# WidgetEsp8266RGBv4Strip.net
KiCad netlist of a schematic drawn in EAGLE
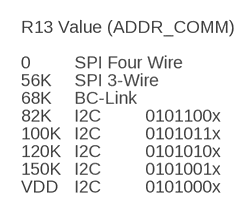
[diagram p0: schematic, sheet 1, part 1 of 3]
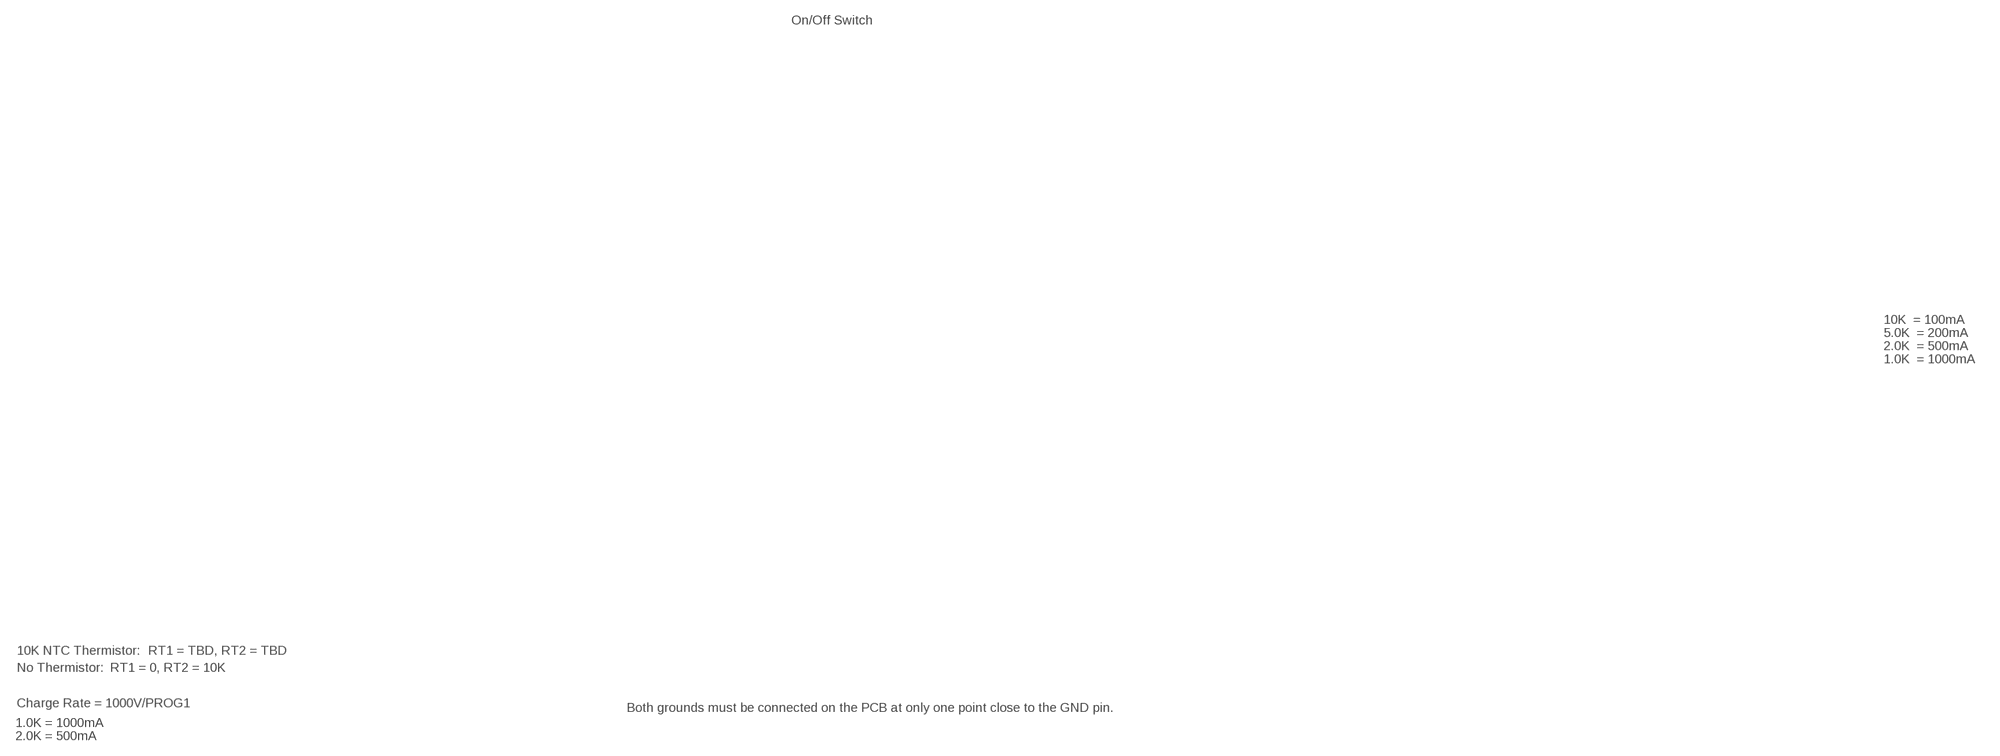
[diagram p1: schematic, sheet 1, part 2 of 3]
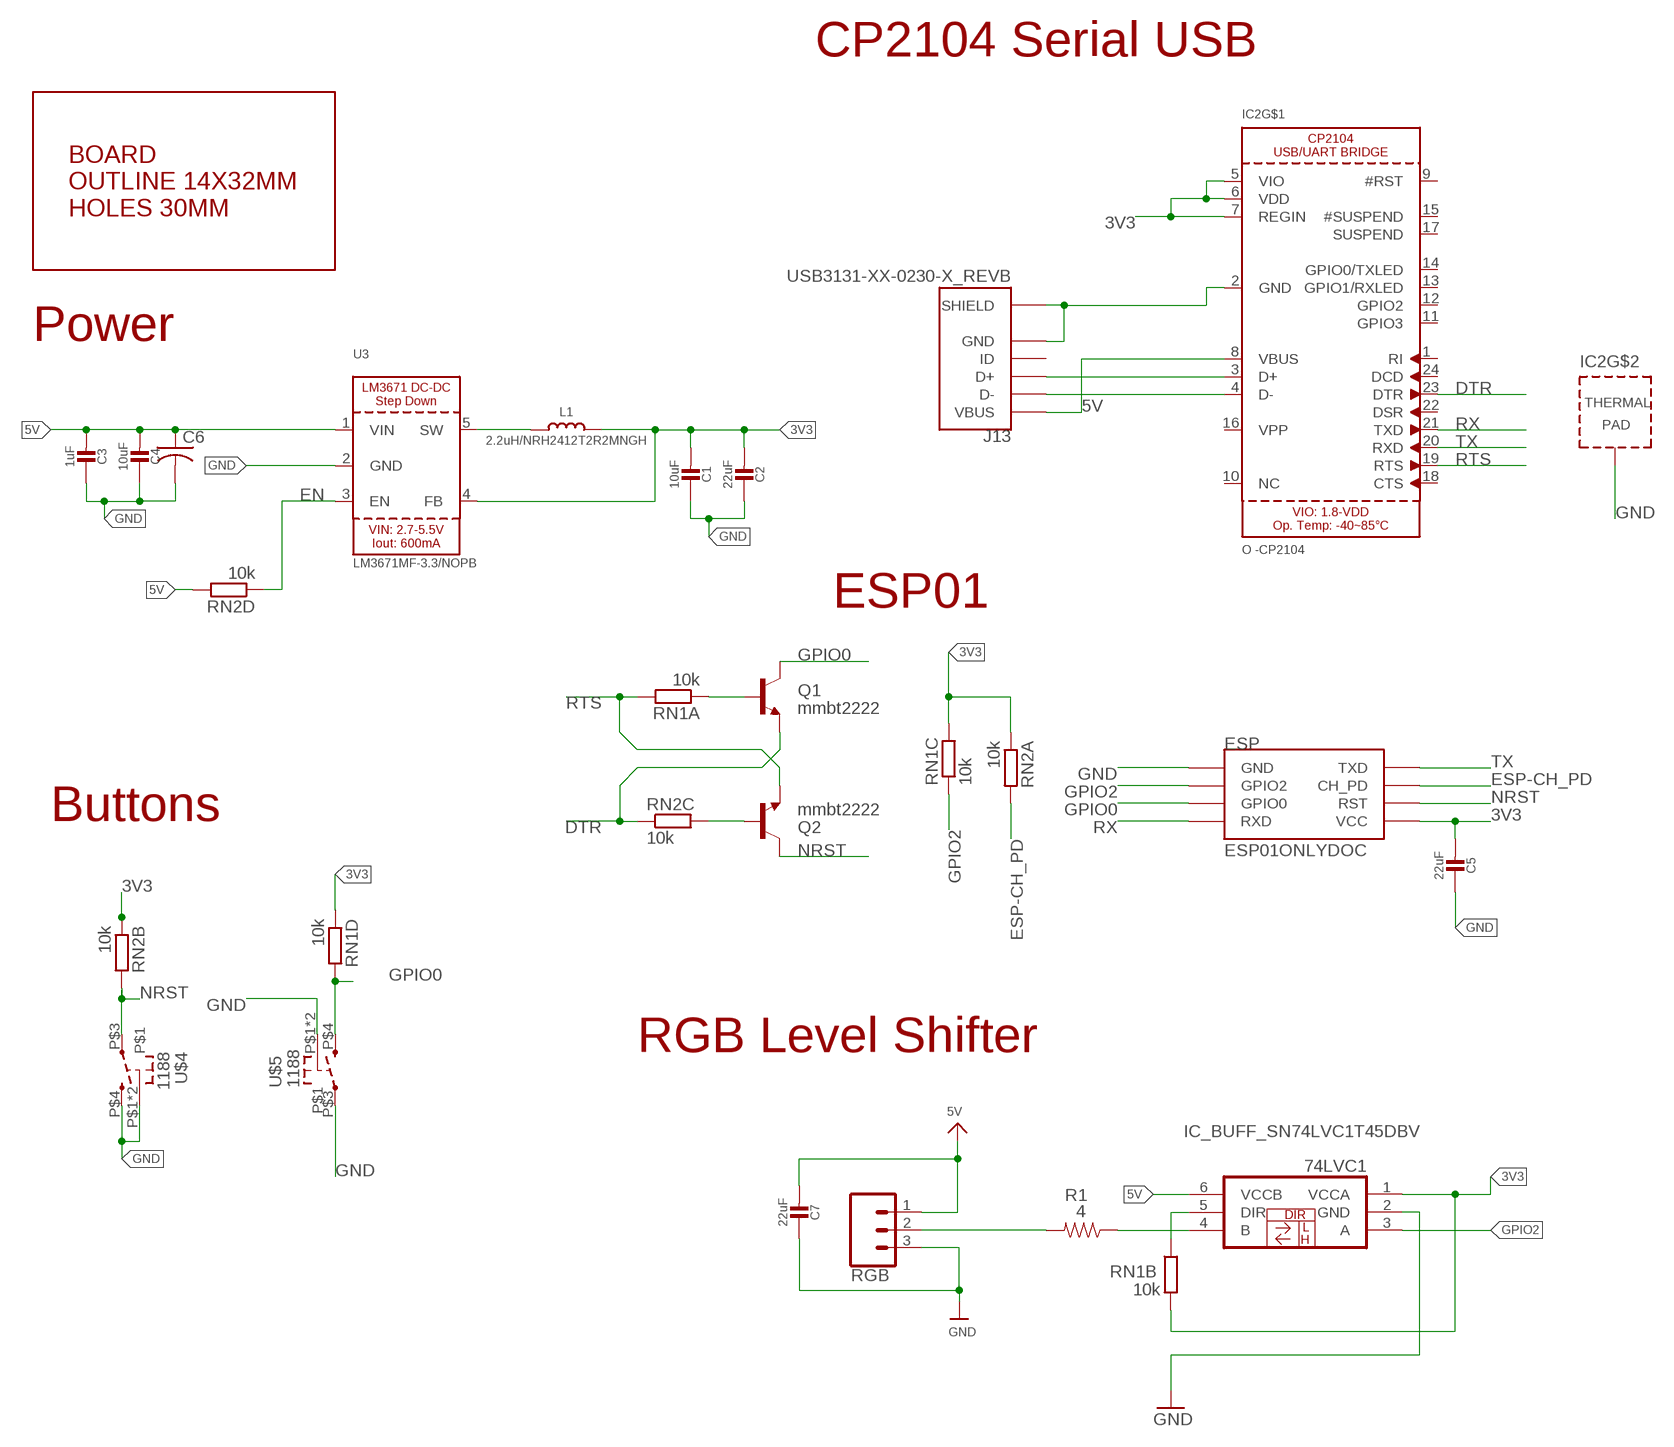
[diagram p2: schematic, sheet 1, part 3 of 3]

(export (version "E")
  (design (tool "Eeschema 10.0.6"))
  (components
    (comp (ref "74LVC1")
      (value "IC_BUFF_SN74LVC1T45DBV")
      (footprint "eagle-import:DBV-R-PDSO-G6")
      (libsource (lib "eagle-import") (part "IC_BUFF_SN74LVC1T45DBV"))
    )
    (comp (ref "C1")
      (value "10uF")
      (footprint "eagle-import:0805-NO")
      (libsource (lib "eagle-import") (part "CAP_CERAMIC0805-NOOUTLINE"))
    )
    (comp (ref "C2")
      (value "22uF")
      (footprint "eagle-import:0805-NO")
      (libsource (lib "eagle-import") (part "CAP_CERAMIC0805-NOOUTLINE"))
    )
    (comp (ref "C3")
      (value "1uF")
      (footprint "eagle-import:0805-NO")
      (libsource (lib "eagle-import") (part "CAP_CERAMIC0805-NOOUTLINE"))
    )
    (comp (ref "C4")
      (value "10uF")
      (footprint "eagle-import:0805-NO")
      (libsource (lib "eagle-import") (part "CAP_CERAMIC0805-NOOUTLINE"))
    )
    (comp (ref "C5")
      (value "22uF")
      (footprint "eagle-import:0805-NO")
      (libsource (lib "eagle-import") (part "CAP_CERAMIC0805-NOOUTLINE"))
    )
    (comp (ref "C6")
      (value "C-USC3225")
      (footprint "eagle-import:C3225")
      (libsource (lib "eagle-import") (part "C-USC3225"))
    )
    (comp (ref "C7")
      (value "22uF")
      (footprint "eagle-import:0805-NO")
      (libsource (lib "eagle-import") (part "CAP_CERAMIC0805-NOOUTLINE"))
    )
    (comp (ref "ESP")
      (value "ESP01ONLYDOC")
      (footprint "eagle-import:ESP01-NONOSILK")
      (libsource (lib "eagle-import") (part "ESP01ONLYDOC"))
    )
    (comp (ref "IC2")
      (value "O -CP2104")
      (footprint "eagle-import:QFN24_4MM_SMSC")
      (libsource (lib "eagle-import") (part "CP2104"))
    )
    (comp (ref "J13")
      (value "USB3131-XX-0230-X_REVB")
      (footprint "eagle-import:GCT_USB3131-XX-0230-X_REVB")
      (fields
        (field (name "MF") "Global Connector Technology")
        (field (name "MP") "USB3131-30-0230-A")
        (field (name "SPICEPREFIX") "X")
      )
      (libsource (lib "eagle-import") (part "USB3131-XX-0230-X_REVB"))
    )
    (comp (ref "L1")
      (value "2.2uH/NRH2412T2R2MNGH")
      (footprint "eagle-import:INDUCTOR_TAIYOYUDEN_NRH2412T")
      (libsource (lib "eagle-import") (part "INDUCTORNRH2412T"))
    )
    (comp (ref "Q1")
      (value "mmbt2222")
      (footprint "eagle-import:SOT23-3")
      (libsource (lib "eagle-import") (part "TRANSISTOR_NPNSOT23-3"))
    )
    (comp (ref "Q2")
      (value "mmbt2222")
      (footprint "eagle-import:SOT23-3")
      (libsource (lib "eagle-import") (part "TRANSISTOR_NPNSOT23-3"))
    )
    (comp (ref "R1")
      (value "4")
      (footprint "eagle-import:0805")
      (libsource (lib "eagle-import") (part "RESISTOR0805-RES"))
    )
    (comp (ref "RGB")
      (value "CONN_03LONGPADS")
      (footprint "eagle-import:1X03_LONGPADS")
      (libsource (lib "eagle-import") (part "CONN_03LONGPADS"))
    )
    (comp (ref "RN1")
      (value "10k")
      (footprint "eagle-import:RN8P-4R-CRA06S")
      (libsource (lib "eagle-import") (part "RESISTOR_ARRAY_4"))
    )
    (comp (ref "RN2")
      (value "10k")
      (footprint "eagle-import:RN8P-4R-CRA06S")
      (libsource (lib "eagle-import") (part "RESISTOR_ARRAY_4"))
    )
    (comp (ref "U$4")
      (value "1188")
      (footprint "eagle-import:1188")
      (libsource (lib "eagle-import") (part "1188"))
    )
    (comp (ref "U$5")
      (value "1188")
      (footprint "eagle-import:1188")
      (libsource (lib "eagle-import") (part "1188"))
    )
    (comp (ref "U$7")
      (value "BOARD14X32")
      (footprint "eagle-import:14X32")
      (libsource (lib "eagle-import") (part "BOARD14X32"))
    )
    (comp (ref "U3")
      (value "LM3671MF-3.3/NOPB")
      (footprint "eagle-import:SOT23-5")
      (libsource (lib "eagle-import") (part "VREG_LM3671"))
    )
  )
  (nets
    (net (code "1") (name "/DTR") (class "Default")
      (node (ref "IC2") (pin "23") (pinfunction "DTR_23") (pintype "output"))
      (node (ref "Q1") (pin "2") (pinfunction "E_2") (pintype "passive"))
      (node (ref "RN2") (pin "3") (pinfunction "1_3") (pintype "passive"))
    )
    (net (code "2") (name "/EN") (class "Default")
      (node (ref "RN2") (pin "4") (pinfunction "1_4") (pintype "passive"))
      (node (ref "U3") (pin "3") (pinfunction "EN_3") (pintype "input"))
    )
    (net (code "3") (name "/ESP-CH_PD") (class "Default")
      (node (ref "ESP") (pin "CH_PD") (pinfunction "CH_PD_CH_PD") (pintype "bidirectional"))
      (node (ref "RN2") (pin "8") (pinfunction "2_8") (pintype "passive"))
    )
    (net (code "4") (name "/GPIO0") (class "Default")
      (node (ref "ESP") (pin "GPIO0") (pinfunction "GPIO0_GPIO0") (pintype "bidirectional"))
      (node (ref "Q1") (pin "3") (pinfunction "C_3") (pintype "passive"))
      (node (ref "RN1") (pin "5") (pinfunction "2_5") (pintype "passive"))
      (node (ref "U$5") (pin "P$4") (pinfunction "3_P$4") (pintype "passive"))
    )
    (net (code "5") (name "/NRST") (class "Default")
      (node (ref "ESP") (pin "RST") (pinfunction "RST_RST") (pintype "bidirectional"))
      (node (ref "Q2") (pin "3") (pinfunction "C_3") (pintype "passive"))
      (node (ref "RN2") (pin "7") (pinfunction "2_7") (pintype "passive"))
      (node (ref "U$4") (pin "P$3") (pinfunction "1_P$3") (pintype "passive"))
    )
    (net (code "6") (name "/RTS") (class "Default")
      (node (ref "IC2") (pin "19") (pinfunction "RTS_19") (pintype "output"))
      (node (ref "Q2") (pin "2") (pinfunction "E_2") (pintype "passive"))
      (node (ref "RN1") (pin "8") (pinfunction "2_8") (pintype "passive"))
    )
    (net (code "7") (name "/RX") (class "Default")
      (node (ref "ESP") (pin "RX") (pinfunction "RXD_RX") (pintype "bidirectional"))
      (node (ref "IC2") (pin "21") (pinfunction "TXD_21") (pintype "output"))
    )
    (net (code "8") (name "/TX") (class "Default")
      (node (ref "ESP") (pin "TX") (pinfunction "TXD_TX") (pintype "bidirectional"))
      (node (ref "IC2") (pin "20") (pinfunction "RXD_20") (pintype "input"))
    )
    (net (code "9") (name "3V3") (class "Default")
      (node (ref "74LVC1") (pin "1") (pinfunction "VCCA_1") (pintype "power_in"))
      (node (ref "C1") (pin "2") (pinfunction "2_2") (pintype "passive"))
      (node (ref "C2") (pin "2") (pinfunction "2_2") (pintype "passive"))
      (node (ref "C5") (pin "2") (pinfunction "2_2") (pintype "passive"))
      (node (ref "ESP") (pin "VCC") (pinfunction "VCC_VCC") (pintype "bidirectional"))
      (node (ref "IC2") (pin "5") (pinfunction "VIO_5") (pintype "power_in"))
      (node (ref "IC2") (pin "6") (pinfunction "VDD_6") (pintype "power_in"))
      (node (ref "IC2") (pin "7") (pinfunction "REGIN_7") (pintype "power_in"))
      (node (ref "L1") (pin "2") (pinfunction "2_2") (pintype "passive"))
      (node (ref "RN1") (pin "4") (pinfunction "1_4") (pintype "passive"))
      (node (ref "RN1") (pin "6") (pinfunction "2_6") (pintype "passive"))
      (node (ref "RN1") (pin "7") (pinfunction "2_7") (pintype "passive"))
      (node (ref "RN2") (pin "1") (pinfunction "1_1") (pintype "passive"))
      (node (ref "RN2") (pin "2") (pinfunction "1_2") (pintype "passive"))
      (node (ref "U3") (pin "4") (pinfunction "FB_4") (pintype "power_in"))
    )
    (net (code "10") (name "5V") (class "Default")
      (node (ref "74LVC1") (pin "6") (pinfunction "VCCB_6") (pintype "power_in"))
      (node (ref "C3") (pin "2") (pinfunction "2_2") (pintype "passive"))
      (node (ref "C4") (pin "2") (pinfunction "2_2") (pintype "passive"))
      (node (ref "C6") (pin "1") (pinfunction "1_1") (pintype "passive"))
      (node (ref "C7") (pin "2") (pinfunction "2_2") (pintype "passive"))
      (node (ref "IC2") (pin "8") (pinfunction "VBUS_8") (pintype "power_in"))
      (node (ref "J13") (pin "1") (pinfunction "VBUS_1") (pintype "power_in"))
      (node (ref "RGB") (pin "1") (pinfunction "1_1") (pintype "passive"))
      (node (ref "RN2") (pin "5") (pinfunction "2_5") (pintype "passive"))
      (node (ref "U3") (pin "1") (pinfunction "VIN_1") (pintype "power_in"))
    )
    (net (code "11") (name "GND") (class "Default")
      (node (ref "74LVC1") (pin "2") (pinfunction "GND_2") (pintype "power_in"))
      (node (ref "C1") (pin "1") (pinfunction "1_1") (pintype "passive"))
      (node (ref "C2") (pin "1") (pinfunction "1_1") (pintype "passive"))
      (node (ref "C3") (pin "1") (pinfunction "1_1") (pintype "passive"))
      (node (ref "C4") (pin "1") (pinfunction "1_1") (pintype "passive"))
      (node (ref "C5") (pin "1") (pinfunction "1_1") (pintype "passive"))
      (node (ref "C6") (pin "2") (pinfunction "2_2") (pintype "passive"))
      (node (ref "C7") (pin "1") (pinfunction "1_1") (pintype "passive"))
      (node (ref "ESP") (pin "GND") (pinfunction "GND_GND") (pintype "bidirectional"))
      (node (ref "IC2") (pin "2") (pinfunction "GND_2") (pintype "power_in"))
      (node (ref "IC2") (pin "THERM") (pinfunction "TP_THERM") (pintype "power_in"))
      (node (ref "J13") (pin "5") (pinfunction "GND_5") (pintype "power_in"))
      (node (ref "J13") (pin "6") (pinfunction "SHIELD_6") (pintype "passive"))
      (node (ref "J13") (pin "7") (pinfunction "SHIELD_7") (pintype "passive"))
      (node (ref "RGB") (pin "3") (pinfunction "3_3") (pintype "passive"))
      (node (ref "U$4") (pin "P$1") (pinfunction "P$1_P$1") (pintype "bidirectional"))
      (node (ref "U$4") (pin "P$2") (pinfunction "P$1_P$2") (pintype "bidirectional"))
      (node (ref "U$4") (pin "P$4") (pinfunction "3_P$4") (pintype "passive"))
      (node (ref "U$5") (pin "P$1") (pinfunction "P$1_P$1") (pintype "bidirectional"))
      (node (ref "U$5") (pin "P$2") (pinfunction "P$1_P$2") (pintype "bidirectional"))
      (node (ref "U$5") (pin "P$3") (pinfunction "1_P$3") (pintype "passive"))
      (node (ref "U3") (pin "2") (pinfunction "GND_2") (pintype "power_in"))
    )
    (net (code "12") (name "GPIO2") (class "Default")
      (node (ref "74LVC1") (pin "3") (pinfunction "A_3") (pintype "bidirectional"))
      (node (ref "ESP") (pin "GPIO2") (pinfunction "GPIO2_GPIO2") (pintype "bidirectional"))
      (node (ref "RN1") (pin "3") (pinfunction "1_3") (pintype "passive"))
    )
    (net (code "13") (name "Net-(74LVC1-B)") (class "Default")
      (node (ref "74LVC1") (pin "4") (pinfunction "B_4") (pintype "bidirectional"))
      (node (ref "R1") (pin "1") (pinfunction "1_1") (pintype "passive"))
    )
    (net (code "14") (name "Net-(74LVC1-DIR)") (class "Default")
      (node (ref "74LVC1") (pin "5") (pinfunction "DIR_5") (pintype "input"))
      (node (ref "RN1") (pin "2") (pinfunction "1_2") (pintype "passive"))
    )
    (net (code "15") (name "Net-(IC2A-D+)") (class "Default")
      (node (ref "IC2") (pin "3") (pinfunction "D+_3") (pintype "bidirectional"))
      (node (ref "J13") (pin "3") (pinfunction "D+_3") (pintype "bidirectional"))
    )
    (net (code "16") (name "Net-(IC2A-D-)") (class "Default")
      (node (ref "IC2") (pin "4") (pinfunction "D-_4") (pintype "bidirectional"))
      (node (ref "J13") (pin "2") (pinfunction "D-_2") (pintype "bidirectional"))
    )
    (net (code "17") (name "Net-(Q1-B)") (class "Default")
      (node (ref "Q1") (pin "1") (pinfunction "B_1") (pintype "passive"))
      (node (ref "RN1") (pin "1") (pinfunction "1_1") (pintype "passive"))
    )
    (net (code "18") (name "Net-(Q2-B)") (class "Default")
      (node (ref "Q2") (pin "1") (pinfunction "B_1") (pintype "passive"))
      (node (ref "RN2") (pin "6") (pinfunction "2_6") (pintype "passive"))
    )
    (net (code "19") (name "Net-(R1-Pad2)") (class "Default")
      (node (ref "R1") (pin "2") (pinfunction "2_2") (pintype "passive"))
      (node (ref "RGB") (pin "2") (pinfunction "2_2") (pintype "passive"))
    )
    (net (code "20") (name "Net-(U3-SW)") (class "Default")
      (node (ref "L1") (pin "1") (pinfunction "1_1") (pintype "passive"))
      (node (ref "U3") (pin "5") (pinfunction "SW_5") (pintype "output"))
    )
    (net (code "21") (name "unconnected-(IC2A-#RST-Pad9)") (class "Default")
      (node (ref "IC2") (pin "9") (pinfunction "#RST_9") (pintype "bidirectional"))
    )
    (net (code "22") (name "unconnected-(IC2A-#SUSPEND-Pad15)") (class "Default")
      (node (ref "IC2") (pin "15") (pinfunction "#SUSPEND_15") (pintype "output"))
    )
    (net (code "23") (name "unconnected-(IC2A-CTS-Pad18)") (class "Default")
      (node (ref "IC2") (pin "18") (pinfunction "CTS_18") (pintype "input"))
    )
    (net (code "24") (name "unconnected-(IC2A-DCD-Pad24)") (class "Default")
      (node (ref "IC2") (pin "24") (pinfunction "DCD_24") (pintype "input"))
    )
    (net (code "25") (name "unconnected-(IC2A-DSR-Pad22)") (class "Default")
      (node (ref "IC2") (pin "22") (pinfunction "DSR_22") (pintype "input"))
    )
    (net (code "26") (name "unconnected-(IC2A-GPIO0{slash}TXLED-Pad14)") (class "Default")
      (node (ref "IC2") (pin "14") (pinfunction "GPIO0/TXLED_14") (pintype "bidirectional"))
    )
    (net (code "27") (name "unconnected-(IC2A-GPIO1{slash}RXLED-Pad13)") (class "Default")
      (node (ref "IC2") (pin "13") (pinfunction "GPIO1/RXLED_13") (pintype "bidirectional"))
    )
    (net (code "28") (name "unconnected-(IC2A-GPIO2-Pad12)") (class "Default")
      (node (ref "IC2") (pin "12") (pinfunction "GPIO2_12") (pintype "bidirectional"))
    )
    (net (code "29") (name "unconnected-(IC2A-GPIO3-Pad11)") (class "Default")
      (node (ref "IC2") (pin "11") (pinfunction "GPIO3_11") (pintype "bidirectional"))
    )
    (net (code "30") (name "unconnected-(IC2A-NC-Pad10)") (class "Default")
      (node (ref "IC2") (pin "10") (pinfunction "NC_10") (pintype "no_connect"))
    )
    (net (code "31") (name "unconnected-(IC2A-RI-Pad1)") (class "Default")
      (node (ref "IC2") (pin "1") (pinfunction "RI_1") (pintype "input"))
    )
    (net (code "32") (name "unconnected-(IC2A-SUSPEND-Pad17)") (class "Default")
      (node (ref "IC2") (pin "17") (pinfunction "SUSPEND_17") (pintype "output"))
    )
    (net (code "33") (name "unconnected-(IC2A-VPP-Pad16)") (class "Default")
      (node (ref "IC2") (pin "16") (pinfunction "VPP_16") (pintype "bidirectional"))
    )
    (net (code "34") (name "unconnected-(J13-ID-Pad4)") (class "Default")
      (node (ref "J13") (pin "4") (pinfunction "ID_4") (pintype "passive"))
    )
  )
)
